# controlBoard.net
KiCad netlist of a schematic drawn in EAGLE
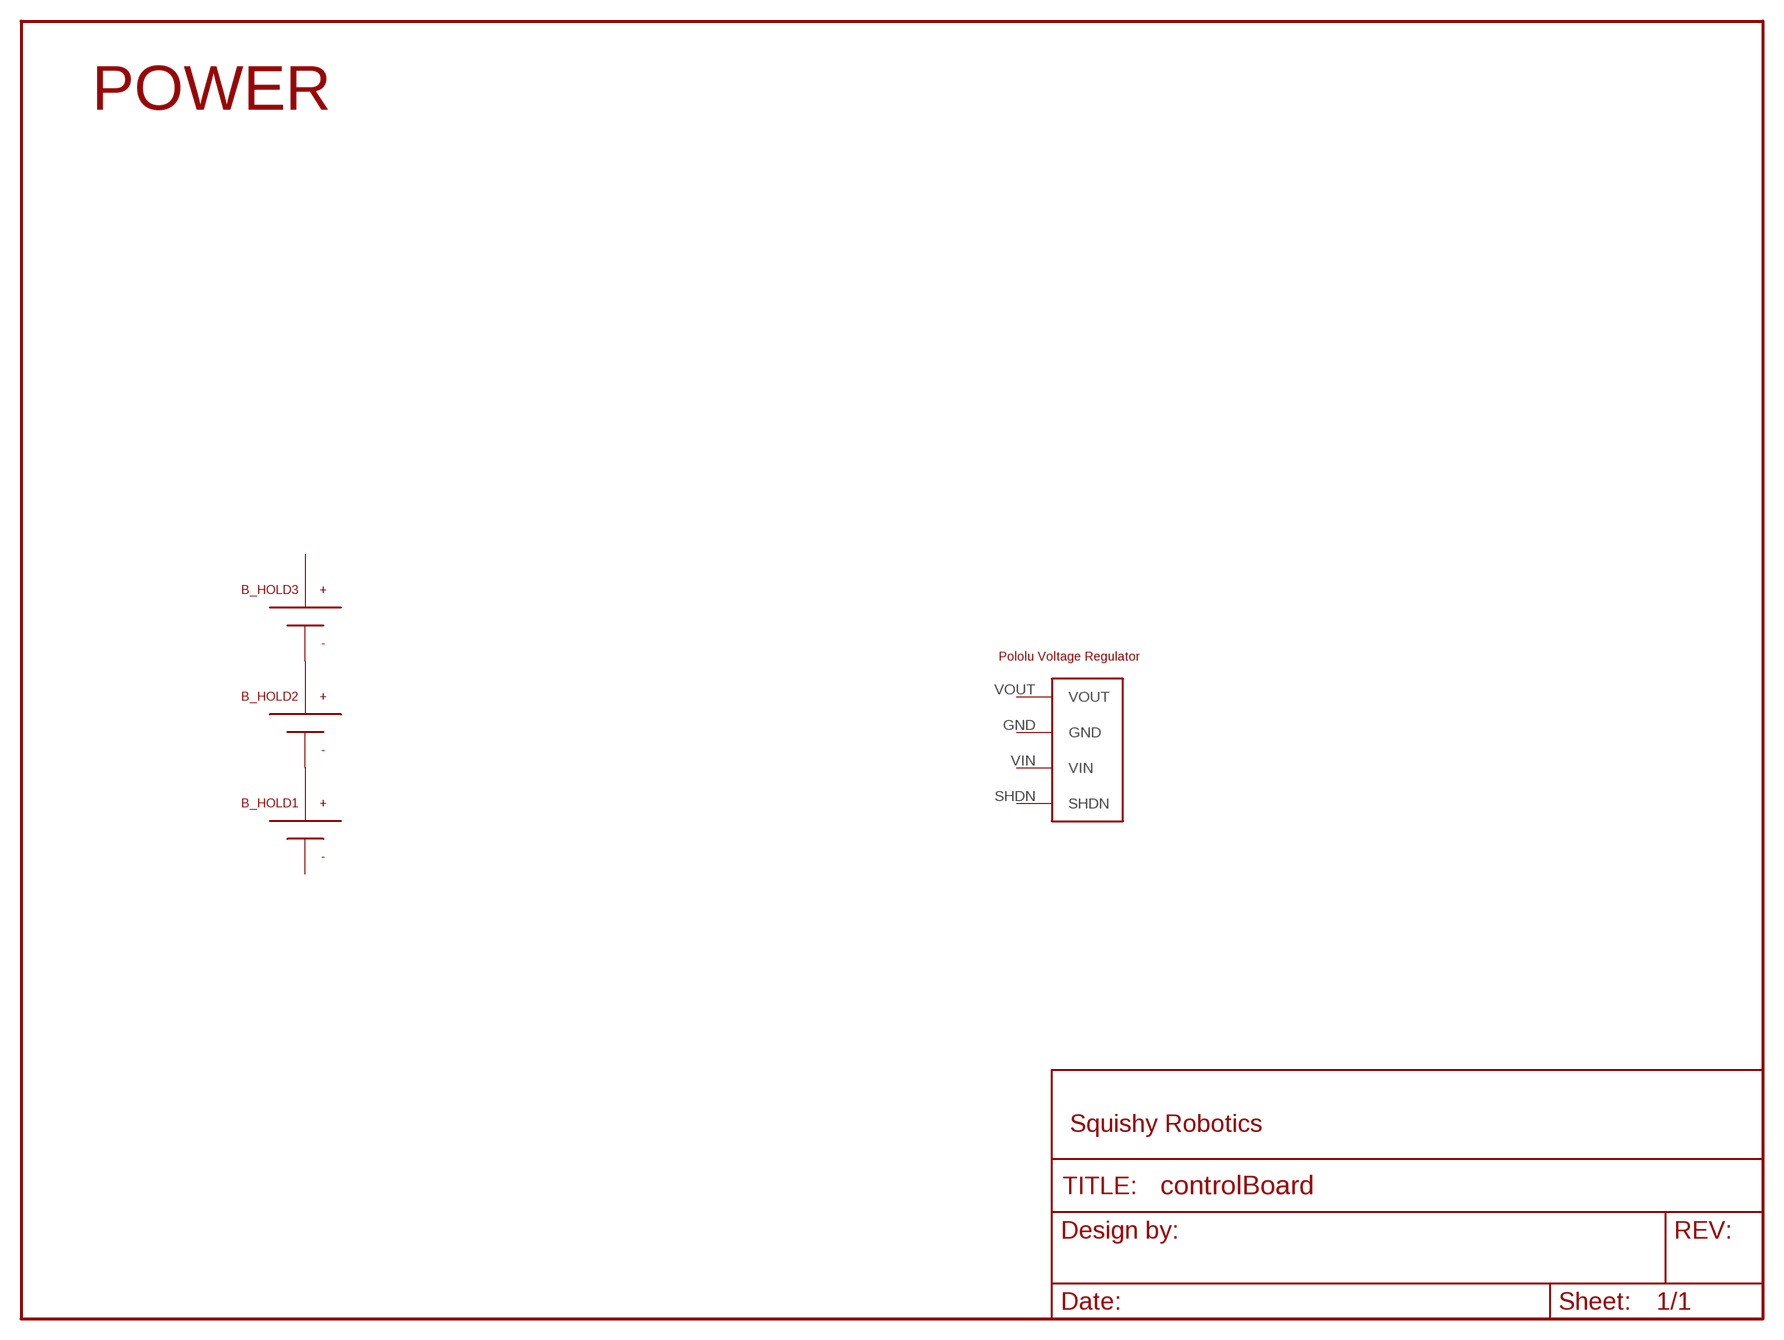
[diagram p0: schematic, sheet 1]

(export (version "E")
  (design (tool "Eeschema 10.0.6"))
  (components
    (comp (ref "B_HOLD1")
      (value "BH-18650-PC-ND")
      (footprint "eagle-import:BH-18650-PC")
      (libsource (lib "eagle-import") (part "BH-18650-PC-ND"))
    )
    (comp (ref "B_HOLD2")
      (value "BH-18650-PC-ND")
      (footprint "eagle-import:BH-18650-PC")
      (libsource (lib "eagle-import") (part "BH-18650-PC-ND"))
    )
    (comp (ref "B_HOLD3")
      (value "BH-18650-PC-ND")
      (footprint "eagle-import:BH-18650-PC")
      (libsource (lib "eagle-import") (part "BH-18650-PC-ND"))
    )
    (comp (ref "U$1")
      (value "POLOLU_VOLTAGE_REGULATOR_D24V5F3")
      (footprint "eagle-import:POLOLU_VOLTAG_REGULATOR_D24V5F3")
      (libsource (lib "eagle-import") (part "POLOLU_VOLTAGE_REGULATOR_D24V5F3"))
    )
  )
  (nets
    (net (code "1") (name "/NEG") (class "Default")
      (node (ref "B_HOLD1") (pin "P$2") (pinfunction "NEG_P$2") (pintype "power_in"))
    )
    (net (code "2") (name "/POS") (class "Default")
      (node (ref "B_HOLD3") (pin "P$1") (pinfunction "POS_P$1") (pintype "power_in"))
    )
    (net (code "3") (name "Net-(B_HOLD1-POS)") (class "Default")
      (node (ref "B_HOLD1") (pin "P$1") (pinfunction "POS_P$1") (pintype "power_in"))
      (node (ref "B_HOLD2") (pin "P$2") (pinfunction "NEG_P$2") (pintype "power_in"))
    )
    (net (code "4") (name "Net-(B_HOLD2-POS)") (class "Default")
      (node (ref "B_HOLD2") (pin "P$1") (pinfunction "POS_P$1") (pintype "power_in"))
      (node (ref "B_HOLD3") (pin "P$2") (pinfunction "NEG_P$2") (pintype "power_in"))
    )
    (net (code "5") (name "unconnected-(U$1-PadGND)") (class "Default")
      (node (ref "U$1") (pin "GND") (pinfunction "GND_GND") (pintype "bidirectional"))
    )
    (net (code "6") (name "unconnected-(U$1-PadSHDN)") (class "Default")
      (node (ref "U$1") (pin "SHDN") (pinfunction "SHDN_SHDN") (pintype "bidirectional"))
    )
    (net (code "7") (name "unconnected-(U$1-PadVIN)") (class "Default")
      (node (ref "U$1") (pin "VIN") (pinfunction "VIN_VIN") (pintype "bidirectional"))
    )
    (net (code "8") (name "unconnected-(U$1-PadVOUT)") (class "Default")
      (node (ref "U$1") (pin "VOUT") (pinfunction "VOUT_VOUT") (pintype "bidirectional"))
    )
  )
)
